# MCU_PART2.net
KiCad netlist of a schematic drawn in Altium Designer
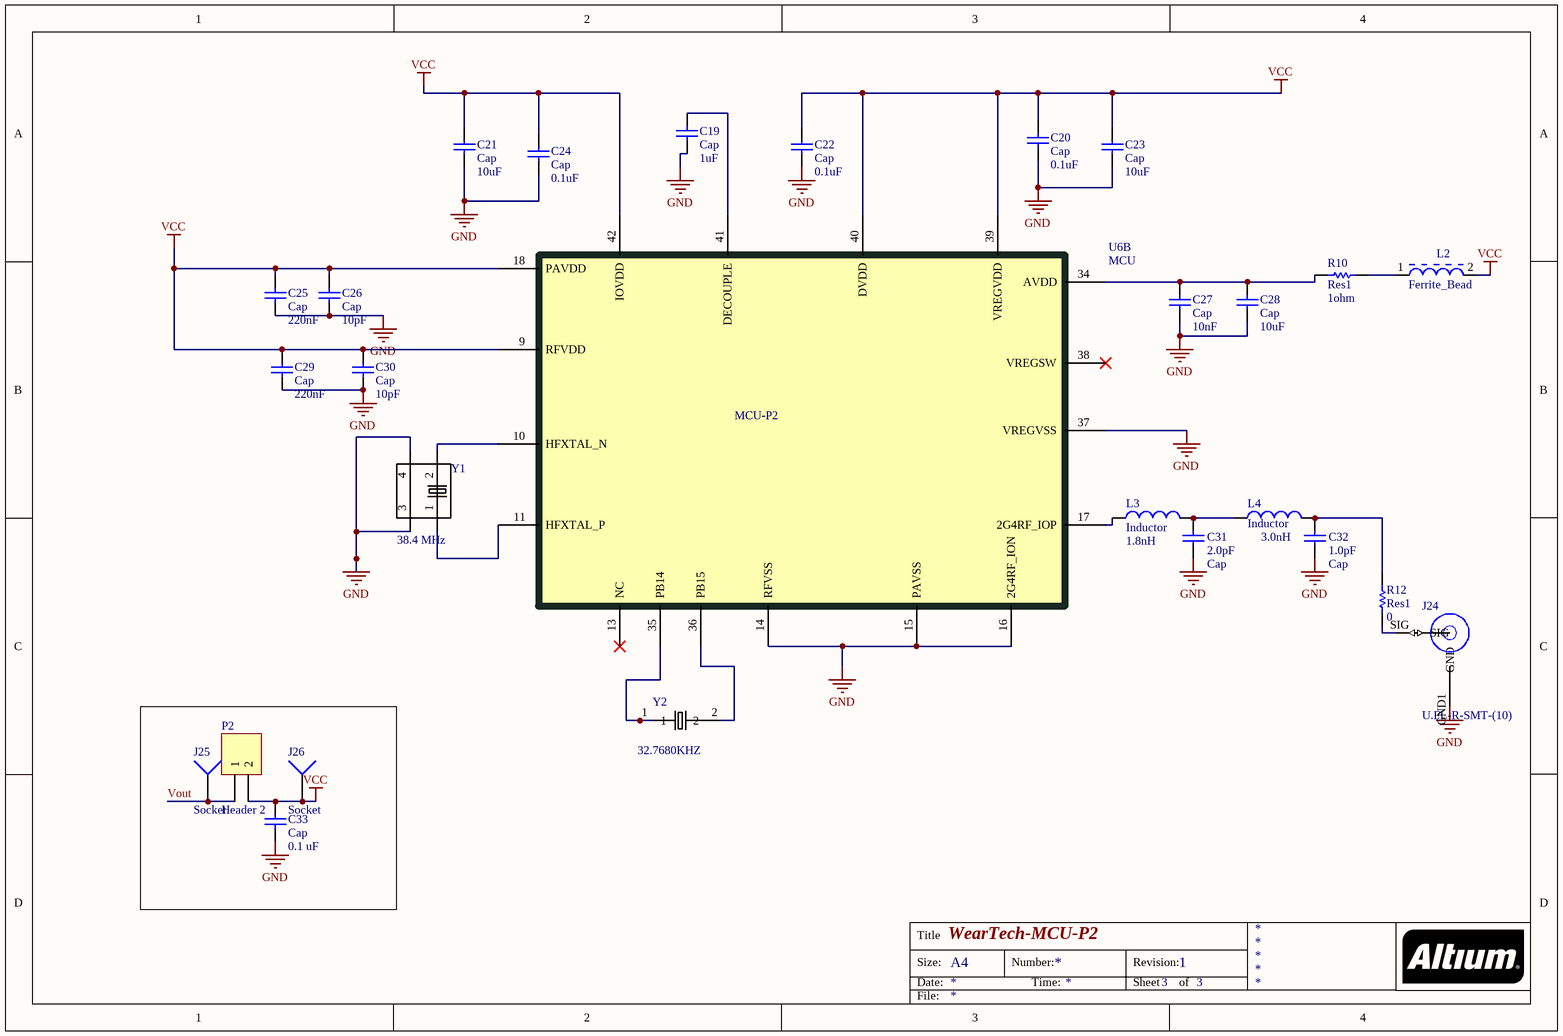
[diagram p0: MCU_PART2.SchDoc]

(export (version "E")
  (design (tool "Eeschema 10.0.6"))
  (components
    (comp (ref "C19")
      (value "Cap")
      (footprint "1608[0603]")
      (description "CAP CER 1UF 25V X5R 0603")
      (fields
        (field (name "ALTIUM_VALUE") "1uF")
        (field (name "MANUFACTURER") "Manufacturer")
        (field (name "DIGIKEY PART NUMBER") "1276-1858-1-ND")
      )
      (libsource (lib "Miscellaneous Devices") (part "Cap"))
    )
    (comp (ref "C20")
      (value "Cap")
      (footprint "1608[0603]")
      (description "CAP CER 0.1UF 16V X7R 0603")
      (fields
        (field (name "ALTIUM_VALUE") "0.1uF")
        (field (name "MANUFACTURER") "Murata Electronics North America")
        (field (name "DIGIKEY PART NUMBER") "490-1532-1-ND")
      )
      (libsource (lib "Miscellaneous Devices") (part "Cap"))
    )
    (comp (ref "C21")
      (value "Cap")
      (footprint "1608[0603]")
      (description "CAP CER 22UF 4V X5R 0603")
      (fields
        (field (name "ALTIUM_VALUE") "10uF")
        (field (name "MANUFACTURER") "Samsung Electro-Mechanics")
        (field (name "DIGIKEY PART NUMBER") "1276-1891-1-ND")
      )
      (libsource (lib "Miscellaneous Devices") (part "Cap"))
    )
    (comp (ref "C22")
      (value "Cap")
      (footprint "1608[0603]")
      (description "CAP CER 0.1UF 16V X7R 0603")
      (fields
        (field (name "ALTIUM_VALUE") "0.1uF")
        (field (name "MANUFACTURER") "Murata Electronics North America")
        (field (name "DIGIKEY PART NUMBER") "490-1532-1-ND")
      )
      (libsource (lib "Miscellaneous Devices") (part "Cap"))
    )
    (comp (ref "C23")
      (value "Cap")
      (footprint "1608[0603]")
      (description "CAP CER 22UF 4V X5R 0603")
      (fields
        (field (name "ALTIUM_VALUE") "10uF")
        (field (name "MANUFACTURER") "Samsung Electro-Mechanics")
        (field (name "DIGIKEY PART NUMBER") "1276-1891-1-ND")
      )
      (libsource (lib "Miscellaneous Devices") (part "Cap"))
    )
    (comp (ref "C24")
      (value "Cap")
      (footprint "1608[0603]")
      (description "CAP CER 0.1UF 16V X7R 0603")
      (fields
        (field (name "ALTIUM_VALUE") "0.1uF")
        (field (name "MANUFACTURER") "Murata Electronics North America")
        (field (name "DIGIKEY PART NUMBER") "490-1532-1-ND")
      )
      (libsource (lib "Miscellaneous Devices") (part "Cap"))
    )
    (comp (ref "C25")
      (value "Cap")
      (footprint "1608[0603]")
      (description "CAP CER 0.22UF 10V X5R 0603")
      (fields
        (field (name "ALTIUM_VALUE") "220nF")
        (field (name "MANUFACTURER") "Murata Electronics North America")
        (field (name "DIGIKEY PART NUMBER") "490-1537-1-ND")
      )
      (libsource (lib "Miscellaneous Devices") (part "Cap"))
    )
    (comp (ref "C26")
      (value "Cap")
      (footprint "1608[0603]")
      (description "CAP CER 10PF 50V C0G/NP0 0603")
      (fields
        (field (name "ALTIUM_VALUE") "10pF")
        (field (name "MANUFACTURER") "Murata Electronics North America")
        (field (name "DIGIKEY PART NUMBER") "490-1403-1-ND")
      )
      (libsource (lib "Miscellaneous Devices") (part "Cap"))
    )
    (comp (ref "C27")
      (value "Cap")
      (footprint "1608[0603]")
      (description "CAP CER 10000PF 10V U2J 0603")
      (fields
        (field (name "ALTIUM_VALUE") "10nF")
        (field (name "MANUFACTURER") "Murata Electronics North America")
        (field (name "DIGIKEY PART NUMBER") "490-8269-1-ND")
      )
      (libsource (lib "Miscellaneous Devices") (part "Cap"))
    )
    (comp (ref "C28")
      (value "Cap")
      (footprint "1608[0603]")
      (description "CAP CER 22UF 4V X5R 0603")
      (fields
        (field (name "ALTIUM_VALUE") "10uF")
        (field (name "MANUFACTURER") "Samsung Electro-Mechanics")
        (field (name "DIGIKEY PART NUMBER") "1276-1891-1-ND")
      )
      (libsource (lib "Miscellaneous Devices") (part "Cap"))
    )
    (comp (ref "C29")
      (value "Cap")
      (footprint "1608[0603]")
      (description "CAP CER 0.22UF 10V X5R 0603")
      (fields
        (field (name "ALTIUM_VALUE") "220nF")
        (field (name "MANUFACTURER") "Murata Electronics North America")
        (field (name "DIGIKEY PART NUMBER") "490-1537-1-ND")
      )
      (libsource (lib "Miscellaneous Devices") (part "Cap"))
    )
    (comp (ref "C30")
      (value "Cap")
      (footprint "1608[0603]")
      (description "CAP CER 10PF 50V C0G/NP0 0603")
      (fields
        (field (name "ALTIUM_VALUE") "10pF")
        (field (name "MANUFACTURER") "Murata Electronics North America")
        (field (name "DIGIKEY PART NUMBER") "490-1403-1-ND")
      )
      (libsource (lib "Miscellaneous Devices") (part "Cap"))
    )
    (comp (ref "C31")
      (value "Cap")
      (footprint "1608[0603]")
      (description "CAP CER 2PF 50V C0G/NP0 0603")
      (fields
        (field (name "ALTIUM_VALUE") "2.0pF")
        (field (name "MANUFACTURER") "Samsung Electro-Mechanics")
        (field (name "DIGIKEY PART NUMBER") "1276-1815-2-ND")
      )
      (libsource (lib "Miscellaneous Devices") (part "Cap"))
    )
    (comp (ref "C32")
      (value "Cap")
      (footprint "1608[0603]")
      (description "CAP CER 1PF 50V C0G/NP0 0603")
      (fields
        (field (name "ALTIUM_VALUE") "1.0pF")
        (field (name "MANUFACTURER") "Murata Electronics North America")
        (field (name "DIGIKEY PART NUMBER") "490-16342-1-ND")
      )
      (libsource (lib "Miscellaneous Devices") (part "Cap"))
    )
    (comp (ref "C33")
      (value "Cap")
      (footprint "1608[0603]")
      (description "CAP CER 0.1UF 16V X7R 0603")
      (fields
        (field (name "ALTIUM_VALUE") "0.1 uF")
        (field (name "MANUFACTURER") "Murata Electronics North America")
        (field (name "DIGIKEY PART NUMBER") "490-1532-1-ND")
      )
      (libsource (lib "Miscellaneous Devices") (part "Cap"))
    )
    (comp (ref "J24")
      (value "U.FL-R-SMT-(10)")
      (description "CONN UMC RCPT STR 50 OHM SMD")
      (fields (field (name "MANUFACTURER") "Molex, LLC") (field (name "DIGIKEY PART NUMBER") "WM5587CT-ND"))
      (libsource (lib "WearTechSchLib") (part "U.FL-R-SMT-(10)"))
    )
    (comp (ref "J25")
      (value "Socket")
      (footprint "PIN1")
      (description "BERGSTRIP .100\" DR STRAIGHT")
      (fields
        (field (name "MANUFACTURER") "Amphenol FCI")
        (field (name "DIGIKEY PART NUMBER") "609-5099-1-ND")
      )
      (libsource (lib "Miscellaneous Connectors") (part "Socket"))
    )
    (comp (ref "J26")
      (value "Socket")
      (footprint "PIN1")
      (description "BERGSTRIP .100\" DR STRAIGHT")
      (fields
        (field (name "MANUFACTURER") "Amphenol FCI")
        (field (name "DIGIKEY PART NUMBER") "609-5099-1-ND")
      )
      (libsource (lib "Miscellaneous Connectors") (part "Socket"))
    )
    (comp (ref "L2")
      (value "Ferrite_Bead")
      (description "FERRITE BEAD 1 KOHM 0603 1LN")
      (fields
        (field (name "MANUFACTURER") "Wurth Electronics Inc.")
        (field (name "DIGIKEY PART NUMBER") "732-4484-1-ND")
      )
      (libsource (lib "WearTechSchLib") (part "Ferrite_Bead"))
    )
    (comp (ref "L3")
      (value "Inductor")
      (footprint "1608[0603]")
      (description "FIXED IND 1.8NH 250MA 400 MOHM")
      (fields
        (field (name "ALTIUM_VALUE") "1.8nH")
        (field (name "MANUFACTURER") "Murata Electronics North America")
        (field (name "DIGIKEY PART NUMBER") "490-11750-1-ND")
      )
      (libsource (lib "Miscellaneous Devices") (part "Inductor"))
    )
    (comp (ref "L4")
      (value "Inductor")
      (footprint "1608[0603]")
      (description "FIXED IND 3NH 670MA 170 MOHM SMD")
      (fields
        (field (name "ALTIUM_VALUE") "3.0nH")
        (field (name "MANUFACTURER") "Murata Electronics North America")
        (field (name "DIGIKEY PART NUMBER") "490-11771-1-ND")
      )
      (libsource (lib "Miscellaneous Devices") (part "Inductor"))
    )
    (comp (ref "P2")
      (value "Header 2")
      (footprint "HDR1X2")
      (description "CONN JUMPER SHORTING GOLD FLASH")
      (fields (field (name "MANUFACTURER") "Sullins Connector Solutions"))
      (libsource (lib "Miscellaneous Connectors") (part "Header 2"))
    )
    (comp (ref "R10")
      (value "Res1")
      (footprint "1608[0603]")
      (description "RES SMD 1 OHM 1% 1/10W 0603")
      (fields
        (field (name "ALTIUM_VALUE") "1ohm")
        (field (name "MANUFACTURER") "Yageo")
        (field (name "DIGIKEY PART NUMBER") "311-1.00HRCT-ND")
      )
      (libsource (lib "Miscellaneous Devices") (part "Res1"))
    )
    (comp (ref "R12")
      (value "Res1")
      (footprint "1608[0603]")
      (description "RES SMD 0 OHM JUMPER 1/10W 0603")
      (fields
        (field (name "ALTIUM_VALUE") "0")
        (field (name "MANUFACTURER") "Yageo")
        (field (name "DIGIKEY PART NUMBER") "311-0.0GRCT-ND")
      )
      (libsource (lib "Miscellaneous Devices") (part "Res1"))
    )
    (comp (ref "U6")
      (value "MCU")
      (footprint "QFN50P700X700X90_HS-49N")
      (description "RF System on a Chip - SoC Blue Premium 19dBm 2.4G 512kB 64kB(RAM)")
      (fields
        (field (name "MANUFACTURER") "Silicon Labs")
        (field (name "MOUSER PART NUMBER") "634-EFR32BG13P732-C")
      )
      (libsource (lib "WearTechSchLib") (part "MCU"))
    )
    (comp (ref "Y1")
      (value "38.4 MHz")
      (description "CRYSTAL 38.4000MHZ 7PF SMD")
      (fields
        (field (name "MANUFACTURER") "AVX Corp/Kyocera Corp")
        (field (name "DIGIKEY PART NUMBER") "1253-1777-1-ND")
      )
      (libsource (lib "WearTechSchLib") (part "X1"))
    )
    (comp (ref "Y2")
      (value "32.7680KHZ")
      (footprint "X2")
      (description "CRYSTAL 32.7680KHZ 12.5PF SMD")
      (fields
        (field (name "MANUFACTURER") "TXC CORPORATION")
        (field (name "DIGIKEY PART NUMBER") "887-1504-1-ND")
      )
      (libsource (lib "WearTechSchLib") (part "X2"))
    )
  )
  (nets
    (net (code "1") (name "/Vout") (class "Default")
      (node (ref "J25") (pin "1") (pinfunction "1_1") (pintype "passive"))
      (node (ref "P2") (pin "1") (pinfunction "1_1") (pintype "passive"))
    )
    (net (code "2") (name "GND") (class "Default")
      (node (ref "C19") (pin "1") (pinfunction "1_1") (pintype "passive"))
      (node (ref "C20") (pin "1") (pinfunction "1_1") (pintype "passive"))
      (node (ref "C21") (pin "1") (pinfunction "1_1") (pintype "passive"))
      (node (ref "C22") (pin "1") (pinfunction "1_1") (pintype "passive"))
      (node (ref "C23") (pin "1") (pinfunction "1_1") (pintype "passive"))
      (node (ref "C24") (pin "1") (pinfunction "1_1") (pintype "passive"))
      (node (ref "C25") (pin "1") (pinfunction "1_1") (pintype "passive"))
      (node (ref "C26") (pin "1") (pinfunction "1_1") (pintype "passive"))
      (node (ref "C27") (pin "1") (pinfunction "1_1") (pintype "passive"))
      (node (ref "C28") (pin "1") (pinfunction "1_1") (pintype "passive"))
      (node (ref "C29") (pin "1") (pinfunction "1_1") (pintype "passive"))
      (node (ref "C30") (pin "1") (pinfunction "1_1") (pintype "passive"))
      (node (ref "C31") (pin "1") (pinfunction "1_1") (pintype "passive"))
      (node (ref "C32") (pin "1") (pinfunction "1_1") (pintype "passive"))
      (node (ref "C33") (pin "1") (pinfunction "1_1") (pintype "passive"))
      (node (ref "J24") (pin "GND1") (pinfunction "GND_GND1") (pintype "passive"))
      (node (ref "U6") (pin "14") (pinfunction "RFVSS_14") (pintype "passive"))
      (node (ref "U6") (pin "15") (pinfunction "PAVSS_15") (pintype "passive"))
      (node (ref "U6") (pin "16") (pinfunction "2G4RF_ION_16") (pintype "passive"))
      (node (ref "U6") (pin "37") (pinfunction "VREGVSS_37") (pintype "passive"))
      (node (ref "Y1") (pin "3") (pinfunction "3_3") (pintype "passive"))
      (node (ref "Y1") (pin "4") (pinfunction "4_4") (pintype "passive"))
    )
    (net (code "3") (name "Net-(C31-Pad2)") (class "Default")
      (node (ref "C31") (pin "2") (pinfunction "2_2") (pintype "passive"))
      (node (ref "L3") (pin "2") (pinfunction "2_2") (pintype "passive"))
      (node (ref "L4") (pin "1") (pinfunction "1_1") (pintype "passive"))
    )
    (net (code "4") (name "Net-(C32-Pad2)") (class "Default")
      (node (ref "C32") (pin "2") (pinfunction "2_2") (pintype "passive"))
      (node (ref "L4") (pin "2") (pinfunction "2_2") (pintype "passive"))
      (node (ref "R12") (pin "2") (pinfunction "2_2") (pintype "passive"))
    )
    (net (code "5") (name "Net-(J24-PadSIG)") (class "Default")
      (node (ref "J24") (pin "SIG") (pinfunction "SIG_SIG") (pintype "bidirectional"))
      (node (ref "R12") (pin "1") (pinfunction "1_1") (pintype "passive"))
    )
    (net (code "6") (name "Net-(L2-Pad1)") (class "Default")
      (node (ref "L2") (pin "1") (pintype "passive"))
      (node (ref "R10") (pin "2") (pinfunction "2_2") (pintype "passive"))
    )
    (net (code "7") (name "Net-(U6B-2G4RF_IOP)") (class "Default")
      (node (ref "L3") (pin "1") (pinfunction "1_1") (pintype "passive"))
      (node (ref "U6") (pin "17") (pinfunction "2G4RF_IOP_17") (pintype "passive"))
    )
    (net (code "8") (name "Net-(U6B-AVDD)") (class "Default")
      (node (ref "C27") (pin "2") (pinfunction "2_2") (pintype "passive"))
      (node (ref "C28") (pin "2") (pinfunction "2_2") (pintype "passive"))
      (node (ref "R10") (pin "1") (pinfunction "1_1") (pintype "passive"))
      (node (ref "U6") (pin "34") (pinfunction "AVDD_34") (pintype "passive"))
    )
    (net (code "9") (name "Net-(U6B-DECOUPLE)") (class "Default")
      (node (ref "C19") (pin "2") (pinfunction "2_2") (pintype "passive"))
      (node (ref "U6") (pin "41") (pinfunction "DECOUPLE_41") (pintype "passive"))
    )
    (net (code "10") (name "Net-(U6B-HFXTAL_N)") (class "Default")
      (node (ref "U6") (pin "10") (pinfunction "HFXTAL_N_10") (pintype "passive"))
      (node (ref "Y1") (pin "2") (pinfunction "2_2") (pintype "passive"))
    )
    (net (code "11") (name "Net-(U6B-HFXTAL_P)") (class "Default")
      (node (ref "U6") (pin "11") (pinfunction "HFXTAL_P_11") (pintype "passive"))
      (node (ref "Y1") (pin "1") (pinfunction "1_1") (pintype "passive"))
    )
    (net (code "12") (name "Net-(U6B-PB14)") (class "Default")
      (node (ref "U6") (pin "35") (pinfunction "PB14_35") (pintype "passive"))
      (node (ref "Y2") (pin "1") (pinfunction "1_1") (pintype "passive"))
    )
    (net (code "13") (name "Net-(U6B-PB15)") (class "Default")
      (node (ref "U6") (pin "36") (pinfunction "PB15_36") (pintype "passive"))
      (node (ref "Y2") (pin "2") (pinfunction "2_2") (pintype "passive"))
    )
    (net (code "14") (name "VCC") (class "Default")
      (node (ref "C20") (pin "2") (pinfunction "2_2") (pintype "passive"))
      (node (ref "C21") (pin "2") (pinfunction "2_2") (pintype "passive"))
      (node (ref "C22") (pin "2") (pinfunction "2_2") (pintype "passive"))
      (node (ref "C23") (pin "2") (pinfunction "2_2") (pintype "passive"))
      (node (ref "C24") (pin "2") (pinfunction "2_2") (pintype "passive"))
      (node (ref "C25") (pin "2") (pinfunction "2_2") (pintype "passive"))
      (node (ref "C26") (pin "2") (pinfunction "2_2") (pintype "passive"))
      (node (ref "C29") (pin "2") (pinfunction "2_2") (pintype "passive"))
      (node (ref "C30") (pin "2") (pinfunction "2_2") (pintype "passive"))
      (node (ref "C33") (pin "2") (pinfunction "2_2") (pintype "passive"))
      (node (ref "J26") (pin "1") (pinfunction "1_1") (pintype "passive"))
      (node (ref "L2") (pin "2") (pintype "passive"))
      (node (ref "P2") (pin "2") (pinfunction "2_2") (pintype "passive"))
      (node (ref "U6") (pin "18") (pinfunction "PAVDD_18") (pintype "passive"))
      (node (ref "U6") (pin "39") (pinfunction "VREGVDD_39") (pintype "passive"))
      (node (ref "U6") (pin "40") (pinfunction "DVDD_40") (pintype "passive"))
      (node (ref "U6") (pin "42") (pinfunction "IOVDD_42") (pintype "passive"))
      (node (ref "U6") (pin "9") (pinfunction "RFVDD_9") (pintype "passive"))
    )
    (net (code "15") (name "unconnected-(U6B-NC-Pad13)") (class "Default")
      (node (ref "U6") (pin "13") (pinfunction "NC_13") (pintype "passive+no_connect"))
    )
    (net (code "16") (name "unconnected-(U6B-VREGSW-Pad38)") (class "Default")
      (node (ref "U6") (pin "38") (pinfunction "VREGSW_38") (pintype "passive+no_connect"))
    )
  )
)
